# board1_esp8266.net
KiCad netlist of a schematic drawn in EAGLE
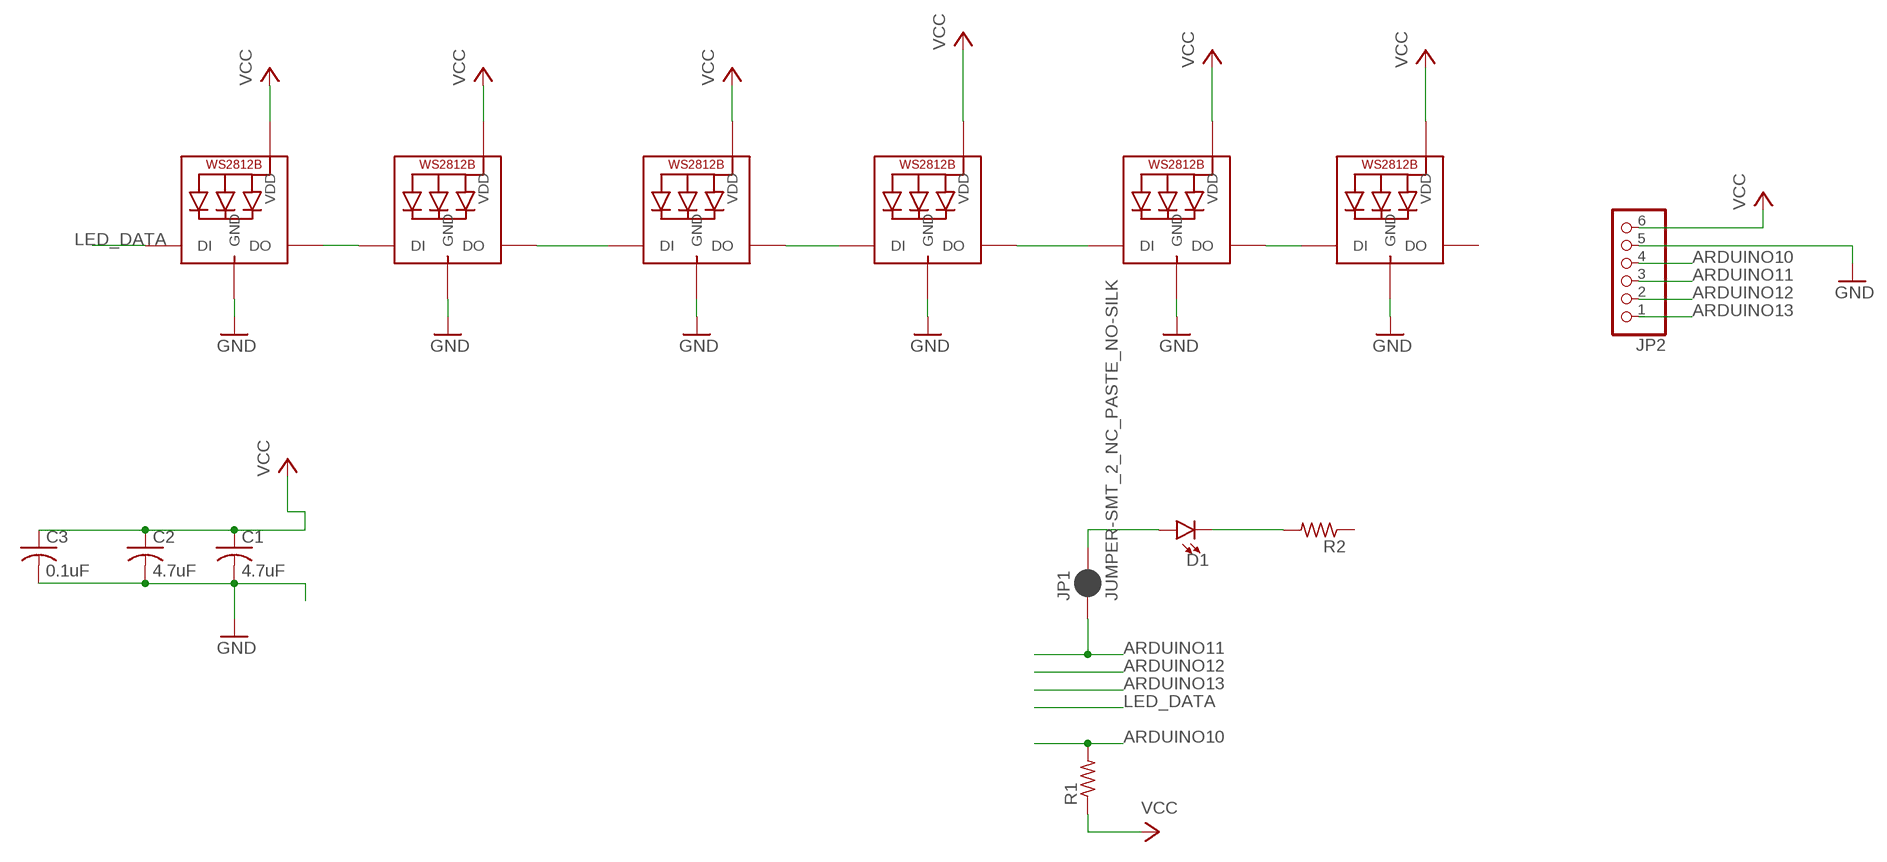
[diagram p0: schematic, sheet 1]

(export (version "E")
  (design (tool "Eeschema 10.0.6"))
  (components
    (comp (ref "C1")
      (value "4.7uF")
      (footprint "eagle-import:C0603")
      (libsource (lib "eagle-import") (part "C-USC0603"))
    )
    (comp (ref "C2")
      (value "4.7uF")
      (footprint "eagle-import:C0603")
      (libsource (lib "eagle-import") (part "C-USC0603"))
    )
    (comp (ref "C3")
      (value "0.1uF")
      (footprint "eagle-import:C0603")
      (libsource (lib "eagle-import") (part "C-USC0603"))
    )
    (comp (ref "D1")
      (value "LED0603")
      (footprint "eagle-import:LED-0603")
      (libsource (lib "eagle-import") (part "LED0603"))
    )
    (comp (ref "JP1")
      (value "JUMPER-SMT_2_NC_PASTE_NO-SILK")
      (footprint "eagle-import:SMT-JUMPER_2_NC_PASTE_NO-SILK")
      (libsource (lib "eagle-import") (part "JUMPER-SMT_2_NC_PASTE_NO-SILK"))
    )
    (comp (ref "JP2")
      (value "PINHD-1X6")
      (footprint "eagle-import:1X06")
      (libsource (lib "eagle-import") (part "PINHD-1X6"))
    )
    (comp (ref "LED1")
      (value "WS2812B5050")
      (footprint "eagle-import:WS2812B")
      (libsource (lib "eagle-import") (part "WS2812B5050"))
    )
    (comp (ref "LED2")
      (value "WS2812B5050")
      (footprint "eagle-import:WS2812B")
      (libsource (lib "eagle-import") (part "WS2812B5050"))
    )
    (comp (ref "LED3")
      (value "WS2812B5050")
      (footprint "eagle-import:WS2812B")
      (libsource (lib "eagle-import") (part "WS2812B5050"))
    )
    (comp (ref "LED4")
      (value "WS2812B5050")
      (footprint "eagle-import:WS2812B")
      (libsource (lib "eagle-import") (part "WS2812B5050"))
    )
    (comp (ref "LED5")
      (value "WS2812B5050")
      (footprint "eagle-import:WS2812B")
      (libsource (lib "eagle-import") (part "WS2812B5050"))
    )
    (comp (ref "LED6")
      (value "WS2812B5050")
      (footprint "eagle-import:WS2812B")
      (libsource (lib "eagle-import") (part "WS2812B5050"))
    )
    (comp (ref "R1")
      (value "R-US_R0603")
      (footprint "eagle-import:R0603")
      (libsource (lib "eagle-import") (part "R-US_R0603"))
    )
    (comp (ref "R2")
      (value "R-US_R0603")
      (footprint "eagle-import:R0603")
      (libsource (lib "eagle-import") (part "R-US_R0603"))
    )
  )
  (nets
    (net (code "1") (name "/ARDUINO10") (class "Default")
      (node (ref "JP2") (pin "4") (pinfunction "4_4") (pintype "passive"))
      (node (ref "R1") (pin "2") (pinfunction "2_2") (pintype "passive"))
    )
    (net (code "2") (name "/ARDUINO11") (class "Default")
      (node (ref "JP1") (pin "1") (pinfunction "1_1") (pintype "passive"))
      (node (ref "JP2") (pin "3") (pinfunction "3_3") (pintype "passive"))
    )
    (net (code "3") (name "/ARDUINO12") (class "Default")
      (node (ref "JP2") (pin "2") (pinfunction "2_2") (pintype "passive"))
    )
    (net (code "4") (name "/ARDUINO13") (class "Default")
      (node (ref "JP2") (pin "1") (pinfunction "1_1") (pintype "passive"))
    )
    (net (code "5") (name "/LED_DATA") (class "Default")
      (node (ref "LED1") (pin "4-DIN") (pinfunction "DI_4-DIN") (pintype "input"))
    )
    (net (code "6") (name "GND") (class "Default")
      (node (ref "C1") (pin "2") (pinfunction "2_2") (pintype "passive"))
      (node (ref "C2") (pin "2") (pinfunction "2_2") (pintype "passive"))
      (node (ref "C3") (pin "2") (pinfunction "2_2") (pintype "passive"))
      (node (ref "JP2") (pin "5") (pinfunction "5_5") (pintype "passive"))
      (node (ref "LED1") (pin "3-GND") (pinfunction "GND_3-GND") (pintype "power_in"))
      (node (ref "LED2") (pin "3-GND") (pinfunction "GND_3-GND") (pintype "power_in"))
      (node (ref "LED3") (pin "3-GND") (pinfunction "GND_3-GND") (pintype "power_in"))
      (node (ref "LED4") (pin "3-GND") (pinfunction "GND_3-GND") (pintype "power_in"))
      (node (ref "LED5") (pin "3-GND") (pinfunction "GND_3-GND") (pintype "power_in"))
      (node (ref "LED6") (pin "3-GND") (pinfunction "GND_3-GND") (pintype "power_in"))
    )
    (net (code "7") (name "Net-(D1-PadA)") (class "Default")
      (node (ref "D1") (pin "A") (pinfunction "A_A") (pintype "passive"))
      (node (ref "JP1") (pin "2") (pinfunction "2_2") (pintype "passive"))
    )
    (net (code "8") (name "Net-(D1-PadC)") (class "Default")
      (node (ref "D1") (pin "C") (pinfunction "C_C") (pintype "passive"))
      (node (ref "R2") (pin "2") (pinfunction "2_2") (pintype "passive"))
    )
    (net (code "9") (name "Net-(LED1-DO)") (class "Default")
      (node (ref "LED1") (pin "2-DOUT") (pinfunction "DO_2-DOUT") (pintype "output"))
      (node (ref "LED2") (pin "4-DIN") (pinfunction "DI_4-DIN") (pintype "input"))
    )
    (net (code "10") (name "Net-(LED2-DO)") (class "Default")
      (node (ref "LED2") (pin "2-DOUT") (pinfunction "DO_2-DOUT") (pintype "output"))
      (node (ref "LED3") (pin "4-DIN") (pinfunction "DI_4-DIN") (pintype "input"))
    )
    (net (code "11") (name "Net-(LED3-DO)") (class "Default")
      (node (ref "LED3") (pin "2-DOUT") (pinfunction "DO_2-DOUT") (pintype "output"))
      (node (ref "LED4") (pin "4-DIN") (pinfunction "DI_4-DIN") (pintype "input"))
    )
    (net (code "12") (name "Net-(LED4-DO)") (class "Default")
      (node (ref "LED4") (pin "2-DOUT") (pinfunction "DO_2-DOUT") (pintype "output"))
      (node (ref "LED5") (pin "4-DIN") (pinfunction "DI_4-DIN") (pintype "input"))
    )
    (net (code "13") (name "Net-(LED5-DO)") (class "Default")
      (node (ref "LED5") (pin "2-DOUT") (pinfunction "DO_2-DOUT") (pintype "output"))
      (node (ref "LED6") (pin "4-DIN") (pinfunction "DI_4-DIN") (pintype "input"))
    )
    (net (code "14") (name "VCC") (class "Default")
      (node (ref "C1") (pin "1") (pinfunction "1_1") (pintype "passive"))
      (node (ref "C2") (pin "1") (pinfunction "1_1") (pintype "passive"))
      (node (ref "C3") (pin "1") (pinfunction "1_1") (pintype "passive"))
      (node (ref "JP2") (pin "6") (pinfunction "6_6") (pintype "passive"))
      (node (ref "LED1") (pin "1-VDD") (pinfunction "VDD_1-VDD") (pintype "power_in"))
      (node (ref "LED2") (pin "1-VDD") (pinfunction "VDD_1-VDD") (pintype "power_in"))
      (node (ref "LED3") (pin "1-VDD") (pinfunction "VDD_1-VDD") (pintype "power_in"))
      (node (ref "LED4") (pin "1-VDD") (pinfunction "VDD_1-VDD") (pintype "power_in"))
      (node (ref "LED5") (pin "1-VDD") (pinfunction "VDD_1-VDD") (pintype "power_in"))
      (node (ref "LED6") (pin "1-VDD") (pinfunction "VDD_1-VDD") (pintype "power_in"))
      (node (ref "R1") (pin "1") (pinfunction "1_1") (pintype "passive"))
    )
    (net (code "15") (name "unconnected-(LED6-DO-Pad2-DOUT)") (class "Default")
      (node (ref "LED6") (pin "2-DOUT") (pinfunction "DO_2-DOUT") (pintype "output"))
    )
    (net (code "16") (name "unconnected-(R2-Pad1)") (class "Default")
      (node (ref "R2") (pin "1") (pinfunction "1_1") (pintype "passive"))
    )
  )
)
